# module_ESP07.net
KiCad netlist of a schematic drawn in EAGLE
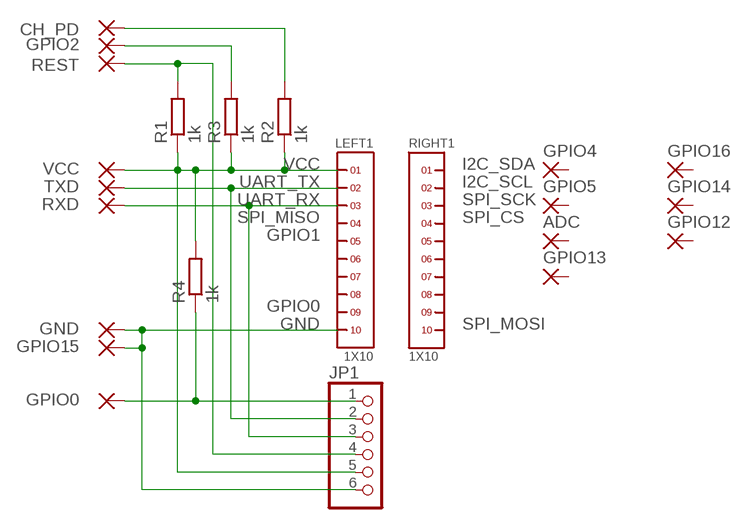
[diagram p0: schematic, sheet 1]

(export (version "E")
  (design (tool "Eeschema 10.0.6"))
  (components
    (comp (ref "ADC")
      (value "WIREPADSMD1,27-254")
      (footprint "eagle-import:SMD1,27-2,54")
      (libsource (lib "eagle-import") (part "WIREPADSMD1,27-254"))
    )
    (comp (ref "CH_PD")
      (value "WIREPADSMD1,27-254")
      (footprint "eagle-import:SMD1,27-2,54")
      (libsource (lib "eagle-import") (part "WIREPADSMD1,27-254"))
    )
    (comp (ref "GND")
      (value "WIREPADSMD1,27-254")
      (footprint "eagle-import:SMD1,27-2,54")
      (libsource (lib "eagle-import") (part "WIREPADSMD1,27-254"))
    )
    (comp (ref "GPIO0")
      (value "WIREPADSMD1,27-254")
      (footprint "eagle-import:SMD1,27-2,54")
      (libsource (lib "eagle-import") (part "WIREPADSMD1,27-254"))
    )
    (comp (ref "GPIO2")
      (value "WIREPADSMD1,27-254")
      (footprint "eagle-import:SMD1,27-2,54")
      (libsource (lib "eagle-import") (part "WIREPADSMD1,27-254"))
    )
    (comp (ref "GPIO4")
      (value "WIREPADSMD1,27-254")
      (footprint "eagle-import:SMD1,27-2,54")
      (libsource (lib "eagle-import") (part "WIREPADSMD1,27-254"))
    )
    (comp (ref "GPIO5")
      (value "WIREPADSMD1,27-254")
      (footprint "eagle-import:SMD1,27-2,54")
      (libsource (lib "eagle-import") (part "WIREPADSMD1,27-254"))
    )
    (comp (ref "GPIO12")
      (value "WIREPADSMD1,27-254")
      (footprint "eagle-import:SMD1,27-2,54")
      (libsource (lib "eagle-import") (part "WIREPADSMD1,27-254"))
    )
    (comp (ref "GPIO13")
      (value "WIREPADSMD1,27-254")
      (footprint "eagle-import:SMD1,27-2,54")
      (libsource (lib "eagle-import") (part "WIREPADSMD1,27-254"))
    )
    (comp (ref "GPIO14")
      (value "WIREPADSMD1,27-254")
      (footprint "eagle-import:SMD1,27-2,54")
      (libsource (lib "eagle-import") (part "WIREPADSMD1,27-254"))
    )
    (comp (ref "GPIO15")
      (value "WIREPADSMD1,27-254")
      (footprint "eagle-import:SMD1,27-2,54")
      (libsource (lib "eagle-import") (part "WIREPADSMD1,27-254"))
    )
    (comp (ref "GPIO16")
      (value "WIREPADSMD1,27-254")
      (footprint "eagle-import:SMD1,27-2,54")
      (libsource (lib "eagle-import") (part "WIREPADSMD1,27-254"))
    )
    (comp (ref "JP1")
      (value "PINHD-1X6")
      (footprint "eagle-import:1X06")
      (libsource (lib "eagle-import") (part "PINHD-1X6"))
    )
    (comp (ref "LEFT1")
      (value "1X10")
      (footprint "eagle-import:1X10")
      (libsource (lib "eagle-import") (part "1X10"))
    )
    (comp (ref "R1")
      (value "1k")
      (footprint "eagle-import:R0603")
      (libsource (lib "eagle-import") (part "R-EU_R0603"))
    )
    (comp (ref "R2")
      (value "1k")
      (footprint "eagle-import:R0603")
      (libsource (lib "eagle-import") (part "R-EU_R0603"))
    )
    (comp (ref "R3")
      (value "1k")
      (footprint "eagle-import:R0603")
      (libsource (lib "eagle-import") (part "R-EU_R0603"))
    )
    (comp (ref "R4")
      (value "1k")
      (footprint "eagle-import:R0603")
      (libsource (lib "eagle-import") (part "R-EU_R0603"))
    )
    (comp (ref "REST")
      (value "WIREPADSMD1,27-254")
      (footprint "eagle-import:SMD1,27-2,54")
      (libsource (lib "eagle-import") (part "WIREPADSMD1,27-254"))
    )
    (comp (ref "RIGHT1")
      (value "1X10")
      (footprint "eagle-import:1X10")
      (libsource (lib "eagle-import") (part "1X10"))
    )
    (comp (ref "RXD")
      (value "WIREPADSMD1,27-254")
      (footprint "eagle-import:SMD1,27-2,54")
      (libsource (lib "eagle-import") (part "WIREPADSMD1,27-254"))
    )
    (comp (ref "TXD")
      (value "WIREPADSMD1,27-254")
      (footprint "eagle-import:SMD1,27-2,54")
      (libsource (lib "eagle-import") (part "WIREPADSMD1,27-254"))
    )
    (comp (ref "VCC")
      (value "WIREPADSMD1,27-254")
      (footprint "eagle-import:SMD1,27-2,54")
      (libsource (lib "eagle-import") (part "WIREPADSMD1,27-254"))
    )
  )
  (nets
    (net (code "1") (name "Net-(CH_PD-P)") (class "Default")
      (node (ref "CH_PD") (pin "1") (pinfunction "P_1") (pintype "passive"))
      (node (ref "R2") (pin "2") (pinfunction "2_2") (pintype "passive"))
    )
    (net (code "2") (name "Net-(GND-P)") (class "Default")
      (node (ref "GND") (pin "1") (pinfunction "P_1") (pintype "passive"))
      (node (ref "GPIO15") (pin "1") (pinfunction "P_1") (pintype "passive"))
      (node (ref "JP1") (pin "6") (pinfunction "6_6") (pintype "passive"))
      (node (ref "LEFT1") (pin "10") (pinfunction "10_10") (pintype "bidirectional"))
    )
    (net (code "3") (name "Net-(GPIO0-P)") (class "Default")
      (node (ref "GPIO0") (pin "1") (pinfunction "P_1") (pintype "passive"))
      (node (ref "JP1") (pin "1") (pinfunction "1_1") (pintype "passive"))
      (node (ref "R4") (pin "1") (pinfunction "1_1") (pintype "passive"))
    )
    (net (code "4") (name "Net-(GPIO2-P)") (class "Default")
      (node (ref "GPIO2") (pin "1") (pinfunction "P_1") (pintype "passive"))
      (node (ref "R3") (pin "2") (pinfunction "2_2") (pintype "passive"))
    )
    (net (code "5") (name "Net-(REST-P)") (class "Default")
      (node (ref "JP1") (pin "4") (pinfunction "4_4") (pintype "passive"))
      (node (ref "R1") (pin "2") (pinfunction "2_2") (pintype "passive"))
      (node (ref "REST") (pin "1") (pinfunction "P_1") (pintype "passive"))
    )
    (net (code "6") (name "Net-(RXD-P)") (class "Default")
      (node (ref "JP1") (pin "3") (pinfunction "3_3") (pintype "passive"))
      (node (ref "LEFT1") (pin "3") (pinfunction "3_3") (pintype "bidirectional"))
      (node (ref "RXD") (pin "1") (pinfunction "P_1") (pintype "passive"))
    )
    (net (code "7") (name "Net-(TXD-P)") (class "Default")
      (node (ref "JP1") (pin "2") (pinfunction "2_2") (pintype "passive"))
      (node (ref "LEFT1") (pin "2") (pinfunction "2_2") (pintype "bidirectional"))
      (node (ref "TXD") (pin "1") (pinfunction "P_1") (pintype "passive"))
    )
    (net (code "8") (name "Net-(VCC-P)") (class "Default")
      (node (ref "JP1") (pin "5") (pinfunction "5_5") (pintype "passive"))
      (node (ref "LEFT1") (pin "1") (pinfunction "1_1") (pintype "bidirectional"))
      (node (ref "R1") (pin "1") (pinfunction "1_1") (pintype "passive"))
      (node (ref "R2") (pin "1") (pinfunction "1_1") (pintype "passive"))
      (node (ref "R3") (pin "1") (pinfunction "1_1") (pintype "passive"))
      (node (ref "R4") (pin "2") (pinfunction "2_2") (pintype "passive"))
      (node (ref "VCC") (pin "1") (pinfunction "P_1") (pintype "passive"))
    )
    (net (code "9") (name "unconnected-(ADC-P-Pad1)") (class "Default")
      (node (ref "ADC") (pin "1") (pinfunction "P_1") (pintype "passive"))
    )
    (net (code "10") (name "unconnected-(GPIO4-P-Pad1)") (class "Default")
      (node (ref "GPIO4") (pin "1") (pinfunction "P_1") (pintype "passive"))
    )
    (net (code "11") (name "unconnected-(GPIO5-P-Pad1)") (class "Default")
      (node (ref "GPIO5") (pin "1") (pinfunction "P_1") (pintype "passive"))
    )
    (net (code "12") (name "unconnected-(GPIO12-P-Pad1)") (class "Default")
      (node (ref "GPIO12") (pin "1") (pinfunction "P_1") (pintype "passive"))
    )
    (net (code "13") (name "unconnected-(GPIO13-P-Pad1)") (class "Default")
      (node (ref "GPIO13") (pin "1") (pinfunction "P_1") (pintype "passive"))
    )
    (net (code "14") (name "unconnected-(GPIO14-P-Pad1)") (class "Default")
      (node (ref "GPIO14") (pin "1") (pinfunction "P_1") (pintype "passive"))
    )
    (net (code "15") (name "unconnected-(GPIO16-P-Pad1)") (class "Default")
      (node (ref "GPIO16") (pin "1") (pinfunction "P_1") (pintype "passive"))
    )
    (net (code "16") (name "unconnected-(LEFT1-Pad4)") (class "Default")
      (node (ref "LEFT1") (pin "4") (pinfunction "4_4") (pintype "bidirectional"))
    )
    (net (code "17") (name "unconnected-(LEFT1-Pad5)") (class "Default")
      (node (ref "LEFT1") (pin "5") (pinfunction "5_5") (pintype "bidirectional"))
    )
    (net (code "18") (name "unconnected-(LEFT1-Pad6)") (class "Default")
      (node (ref "LEFT1") (pin "6") (pinfunction "6_6") (pintype "bidirectional"))
    )
    (net (code "19") (name "unconnected-(LEFT1-Pad7)") (class "Default")
      (node (ref "LEFT1") (pin "7") (pinfunction "7_7") (pintype "bidirectional"))
    )
    (net (code "20") (name "unconnected-(LEFT1-Pad8)") (class "Default")
      (node (ref "LEFT1") (pin "8") (pinfunction "8_8") (pintype "bidirectional"))
    )
    (net (code "21") (name "unconnected-(LEFT1-Pad9)") (class "Default")
      (node (ref "LEFT1") (pin "9") (pinfunction "9_9") (pintype "bidirectional"))
    )
    (net (code "22") (name "unconnected-(RIGHT1-Pad1)") (class "Default")
      (node (ref "RIGHT1") (pin "1") (pinfunction "1_1") (pintype "bidirectional"))
    )
    (net (code "23") (name "unconnected-(RIGHT1-Pad2)") (class "Default")
      (node (ref "RIGHT1") (pin "2") (pinfunction "2_2") (pintype "bidirectional"))
    )
    (net (code "24") (name "unconnected-(RIGHT1-Pad3)") (class "Default")
      (node (ref "RIGHT1") (pin "3") (pinfunction "3_3") (pintype "bidirectional"))
    )
    (net (code "25") (name "unconnected-(RIGHT1-Pad4)") (class "Default")
      (node (ref "RIGHT1") (pin "4") (pinfunction "4_4") (pintype "bidirectional"))
    )
    (net (code "26") (name "unconnected-(RIGHT1-Pad5)") (class "Default")
      (node (ref "RIGHT1") (pin "5") (pinfunction "5_5") (pintype "bidirectional"))
    )
    (net (code "27") (name "unconnected-(RIGHT1-Pad6)") (class "Default")
      (node (ref "RIGHT1") (pin "6") (pinfunction "6_6") (pintype "bidirectional"))
    )
    (net (code "28") (name "unconnected-(RIGHT1-Pad7)") (class "Default")
      (node (ref "RIGHT1") (pin "7") (pinfunction "7_7") (pintype "bidirectional"))
    )
    (net (code "29") (name "unconnected-(RIGHT1-Pad8)") (class "Default")
      (node (ref "RIGHT1") (pin "8") (pinfunction "8_8") (pintype "bidirectional"))
    )
    (net (code "30") (name "unconnected-(RIGHT1-Pad9)") (class "Default")
      (node (ref "RIGHT1") (pin "9") (pinfunction "9_9") (pintype "bidirectional"))
    )
    (net (code "31") (name "unconnected-(RIGHT1-Pad10)") (class "Default")
      (node (ref "RIGHT1") (pin "10") (pinfunction "10_10") (pintype "bidirectional"))
    )
  )
)
